# DS112-1_0-B.net
KiCad netlist of a schematic drawn in Altium Designer
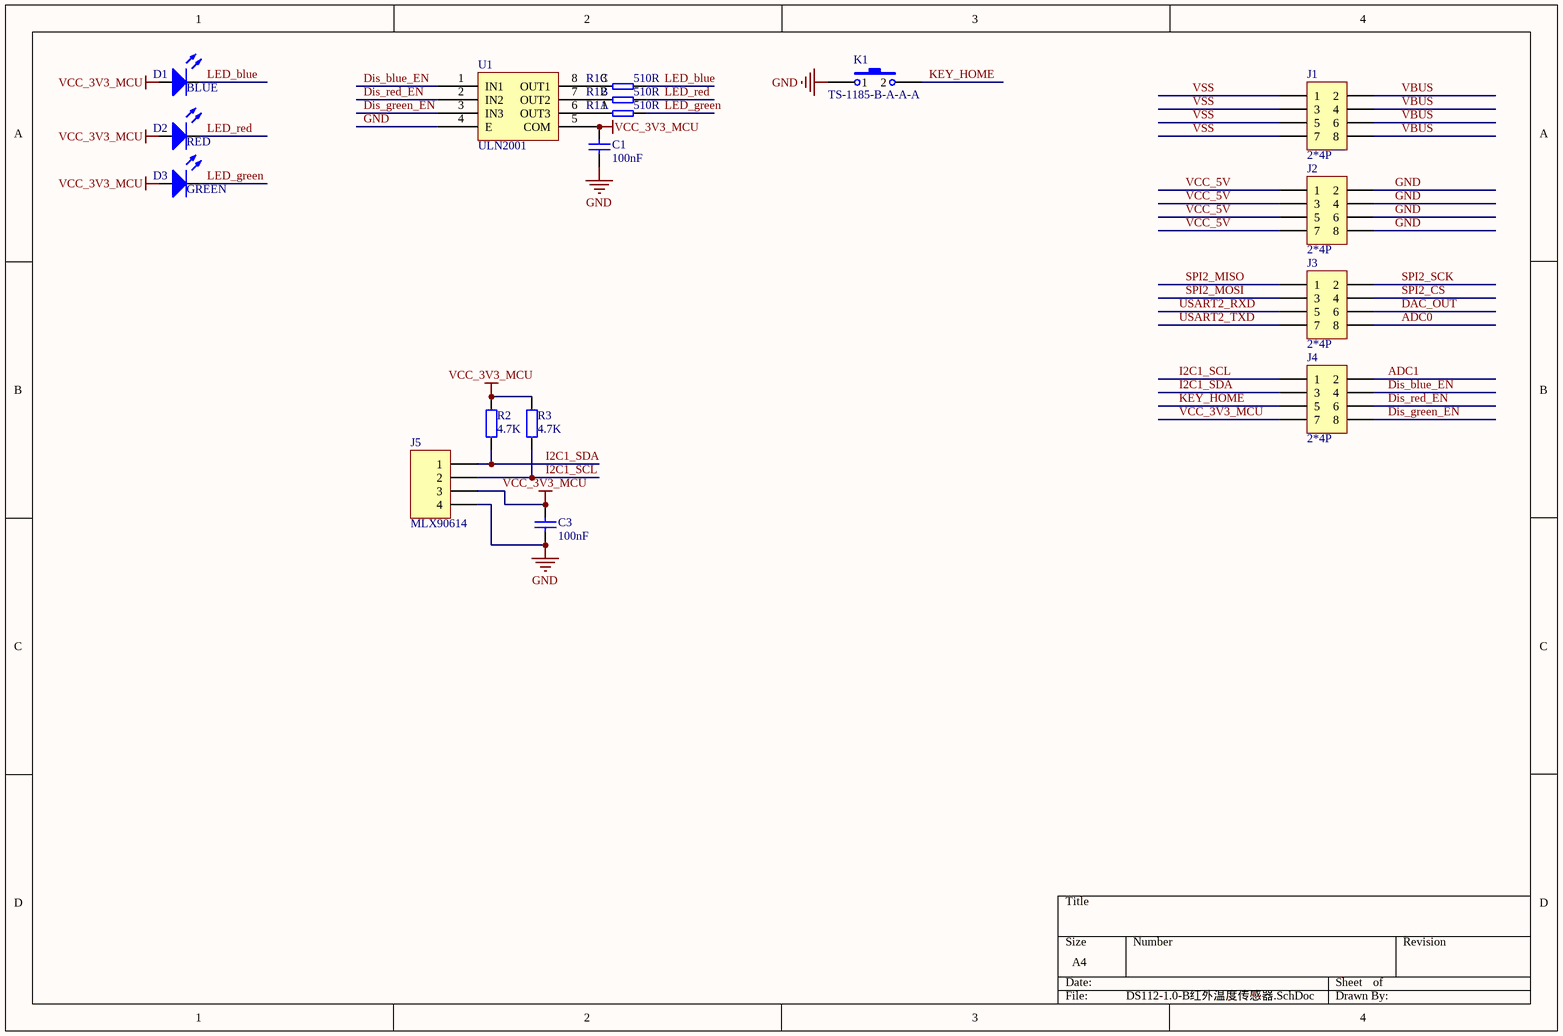
[diagram p0: DS112-1.0-B红外温度传感器.SchDoc]

(export (version "E")
  (design (tool "Eeschema 10.0.6"))
  (components
    (comp (ref "C1")
      (value "100nF")
      (footprint "0603CAP")
      (description "贴片电容")
      (fields (field (name "Comment") "SMDCAP00013"))
      (libsource (lib "AD_SCH") (part "MLCC 100nF 50V ±10％ 0603"))
    )
    (comp (ref "C3")
      (value "100nF")
      (footprint "0603CAP")
      (description "贴片电容")
      (fields (field (name "Comment") "SMDCAP00013"))
      (libsource (lib "AD_SCH") (part "MLCC 100nF 50V ±10％ 0603"))
    )
    (comp (ref "D1")
      (value "BLUE")
      (footprint "LED_0805")
      (description "贴片LED")
      (fields (field (name "Comment") "SMDLED00010"))
      (libsource (lib "AD_SCH") (part "Chip 蓝色LED 0805"))
    )
    (comp (ref "D2")
      (value "RED")
      (footprint "LED_0805")
      (description "贴片LED")
      (fields (field (name "Comment") "SMDLED00003"))
      (libsource (lib "AD_SCH") (part "Chip 红色LED 0805"))
    )
    (comp (ref "D3")
      (value "GREEN")
      (footprint "LED_0805")
      (description "贴片LED")
      (fields (field (name "Comment") "Chip 翠绿LED 0805"))
      (libsource (lib "AD_SCH") (part "Chip 翠绿LED 0805"))
    )
    (comp (ref "J1")
      (value "2*4P")
      (footprint "X1321WVS-2x04J-C40D53")
      (description "双排针2x4P 立贴 1.27mm")
      (fields (field (name "Comment") "X1321WVS-2x04J-C40D53"))
      (libsource (lib "AD_SCH") (part "X1321WVS-2x04J-C40D53"))
    )
    (comp (ref "J2")
      (value "2*4P")
      (footprint "X1321WVS-2x04J-C40D53")
      (description "双排针2x4P 立贴 1.27mm")
      (fields (field (name "Comment") "X1321WVS-2x04J-C40D53"))
      (libsource (lib "AD_SCH") (part "X1321WVS-2x04J-C40D53"))
    )
    (comp (ref "J3")
      (value "2*4P")
      (footprint "X1321WVS-2x04J-C40D53")
      (description "双排针2x4P 立贴 1.27mm")
      (fields (field (name "Comment") "X1321WVS-2x04J-C40D53"))
      (libsource (lib "AD_SCH") (part "X1321WVS-2x04J-C40D53"))
    )
    (comp (ref "J4")
      (value "2*4P")
      (footprint "X1321WVS-2x04J-C40D53")
      (description "双排针2x4P 立贴 1.27mm")
      (fields (field (name "Comment") "X1321WVS-2x04J-C40D53"))
      (libsource (lib "AD_SCH") (part "X1321WVS-2x04J-C40D53"))
    )
    (comp (ref "J5")
      (value "MLX90614")
      (footprint "SIP4")
      (description "单排母座")
      (fields (field (name "Comment") "SL000000047"))
      (libsource (lib "AD_SCH") (part "DIP4 单排母座 间距2.54mm 铜"))
    )
    (comp (ref "K1")
      (value "TS-1185-B-A-A-A")
      (footprint "KEY_TS-1185-x-A-A-A")
      (description "轻触开关")
      (libsource (lib "AD_SCH") (part "TS-1185-B-A-A-A"))
    )
    (comp (ref "R1")
      (value "510R")
      (footprint "0603RES_Pack4")
      (description "贴片排阻")
      (fields (field (name "Comment") "SMDRES05003"))
      (libsource (lib "AD_SCH") (part "Chip R*4 510R 1/16W ±5％ 0603"))
    )
    (comp (ref "R2")
      (value "4.7K")
      (footprint "0603RES")
      (description "贴片电阻")
      (fields (field (name "Comment") "SMDRES00047"))
      (libsource (lib "AD_SCH") (part "Chip 4.7K 1/16W ±1％ 0603"))
    )
    (comp (ref "R3")
      (value "4.7K")
      (footprint "0603RES")
      (description "贴片电阻")
      (fields (field (name "Comment") "SMDRES00047"))
      (libsource (lib "AD_SCH") (part "Chip 4.7K 1/16W ±1％ 0603"))
    )
    (comp (ref "U1")
      (value "ULN2001")
      (footprint "SO-8")
      (description "电机驱动芯片")
      (fields (field (name "Comment") "SMDIC000018"))
      (libsource (lib "AD_SCH") (part "ULN2001 SOP-8"))
    )
  )
  (nets
    (net (code "1") (name "/ADC0") (class "Default")
      (node (ref "J3") (pin "8") (pinfunction "8_8") (pintype "passive"))
    )
    (net (code "2") (name "/ADC1") (class "Default")
      (node (ref "J4") (pin "2") (pinfunction "2_2") (pintype "passive"))
    )
    (net (code "3") (name "/DAC_OUT") (class "Default")
      (node (ref "J3") (pin "6") (pinfunction "6_6") (pintype "passive"))
    )
    (net (code "4") (name "/Dis_blue_EN") (class "Default")
      (node (ref "J4") (pin "4") (pinfunction "4_4") (pintype "passive"))
      (node (ref "U1") (pin "1") (pinfunction "IN1_1") (pintype "passive"))
    )
    (net (code "5") (name "/Dis_green_EN") (class "Default")
      (node (ref "J4") (pin "8") (pinfunction "8_8") (pintype "passive"))
      (node (ref "U1") (pin "3") (pinfunction "IN3_3") (pintype "passive"))
    )
    (net (code "6") (name "/Dis_red_EN") (class "Default")
      (node (ref "J4") (pin "6") (pinfunction "6_6") (pintype "passive"))
      (node (ref "U1") (pin "2") (pinfunction "IN2_2") (pintype "passive"))
    )
    (net (code "7") (name "/I2C1_SCL") (class "Default")
      (node (ref "J4") (pin "1") (pinfunction "1_1") (pintype "passive"))
      (node (ref "J5") (pin "2") (pinfunction "2_2") (pintype "passive"))
      (node (ref "R3") (pin "1") (pinfunction "1_1") (pintype "passive"))
    )
    (net (code "8") (name "/I2C1_SDA") (class "Default")
      (node (ref "J4") (pin "3") (pinfunction "3_3") (pintype "passive"))
      (node (ref "J5") (pin "1") (pinfunction "1_1") (pintype "passive"))
      (node (ref "R2") (pin "1") (pinfunction "1_1") (pintype "passive"))
    )
    (net (code "9") (name "/KEY_HOME") (class "Default")
      (node (ref "J4") (pin "5") (pinfunction "5_5") (pintype "passive"))
      (node (ref "K1") (pin "2") (pinfunction "2_2") (pintype "passive"))
    )
    (net (code "10") (name "/LED_blue") (class "Default")
      (node (ref "D1") (pin "2") (pinfunction "K_2") (pintype "passive"))
      (node (ref "R1") (pin "6") (pinfunction "6_6") (pintype "passive"))
    )
    (net (code "11") (name "/LED_green") (class "Default")
      (node (ref "D3") (pin "2") (pinfunction "K_2") (pintype "passive"))
      (node (ref "R1") (pin "8") (pinfunction "8_8") (pintype "passive"))
    )
    (net (code "12") (name "/LED_red") (class "Default")
      (node (ref "D2") (pin "2") (pinfunction "K_2") (pintype "passive"))
      (node (ref "R1") (pin "7") (pinfunction "7_7") (pintype "passive"))
    )
    (net (code "13") (name "/SPI2_CS") (class "Default")
      (node (ref "J3") (pin "4") (pinfunction "4_4") (pintype "passive"))
    )
    (net (code "14") (name "/SPI2_MISO") (class "Default")
      (node (ref "J3") (pin "1") (pinfunction "1_1") (pintype "passive"))
    )
    (net (code "15") (name "/SPI2_MOSI") (class "Default")
      (node (ref "J3") (pin "3") (pinfunction "3_3") (pintype "passive"))
    )
    (net (code "16") (name "/SPI2_SCK") (class "Default")
      (node (ref "J3") (pin "2") (pinfunction "2_2") (pintype "passive"))
    )
    (net (code "17") (name "/USART2_RXD") (class "Default")
      (node (ref "J3") (pin "5") (pinfunction "5_5") (pintype "passive"))
    )
    (net (code "18") (name "/USART2_TXD") (class "Default")
      (node (ref "J3") (pin "7") (pinfunction "7_7") (pintype "passive"))
    )
    (net (code "19") (name "/VBUS") (class "Default")
      (node (ref "J1") (pin "2") (pinfunction "2_2") (pintype "passive"))
      (node (ref "J1") (pin "4") (pinfunction "4_4") (pintype "passive"))
      (node (ref "J1") (pin "6") (pinfunction "6_6") (pintype "passive"))
      (node (ref "J1") (pin "8") (pinfunction "8_8") (pintype "passive"))
    )
    (net (code "20") (name "/VCC_5V") (class "Default")
      (node (ref "J2") (pin "1") (pinfunction "1_1") (pintype "passive"))
      (node (ref "J2") (pin "3") (pinfunction "3_3") (pintype "passive"))
      (node (ref "J2") (pin "5") (pinfunction "5_5") (pintype "passive"))
      (node (ref "J2") (pin "7") (pinfunction "7_7") (pintype "passive"))
    )
    (net (code "21") (name "/VSS") (class "Default")
      (node (ref "J1") (pin "1") (pinfunction "1_1") (pintype "passive"))
      (node (ref "J1") (pin "3") (pinfunction "3_3") (pintype "passive"))
      (node (ref "J1") (pin "5") (pinfunction "5_5") (pintype "passive"))
      (node (ref "J1") (pin "7") (pinfunction "7_7") (pintype "passive"))
    )
    (net (code "22") (name "GND") (class "Default")
      (node (ref "C1") (pin "1") (pinfunction "1_1") (pintype "passive"))
      (node (ref "C3") (pin "1") (pinfunction "1_1") (pintype "passive"))
      (node (ref "J2") (pin "2") (pinfunction "2_2") (pintype "passive"))
      (node (ref "J2") (pin "4") (pinfunction "4_4") (pintype "passive"))
      (node (ref "J2") (pin "6") (pinfunction "6_6") (pintype "passive"))
      (node (ref "J2") (pin "8") (pinfunction "8_8") (pintype "passive"))
      (node (ref "J5") (pin "4") (pinfunction "4_4") (pintype "passive"))
      (node (ref "K1") (pin "1") (pinfunction "1_1") (pintype "passive"))
      (node (ref "U1") (pin "4") (pinfunction "E_4") (pintype "passive"))
    )
    (net (code "23") (name "Net-(U1-OUT1)") (class "Default")
      (node (ref "R1") (pin "3") (pinfunction "3_3") (pintype "passive"))
      (node (ref "U1") (pin "8") (pinfunction "OUT1_8") (pintype "passive"))
    )
    (net (code "24") (name "Net-(U1-OUT2)") (class "Default")
      (node (ref "R1") (pin "2") (pinfunction "2_2") (pintype "passive"))
      (node (ref "U1") (pin "7") (pinfunction "OUT2_7") (pintype "passive"))
    )
    (net (code "25") (name "Net-(U1-OUT3)") (class "Default")
      (node (ref "R1") (pin "1") (pinfunction "1_1") (pintype "passive"))
      (node (ref "U1") (pin "6") (pinfunction "OUT3_6") (pintype "passive"))
    )
    (net (code "26") (name "VCC_3V3_MCU") (class "Default")
      (node (ref "C1") (pin "2") (pinfunction "2_2") (pintype "passive"))
      (node (ref "C3") (pin "2") (pinfunction "2_2") (pintype "passive"))
      (node (ref "D1") (pin "1") (pinfunction "A_1") (pintype "passive"))
      (node (ref "D2") (pin "1") (pinfunction "A_1") (pintype "passive"))
      (node (ref "D3") (pin "1") (pinfunction "A_1") (pintype "passive"))
      (node (ref "J4") (pin "7") (pinfunction "7_7") (pintype "passive"))
      (node (ref "J5") (pin "3") (pinfunction "3_3") (pintype "passive"))
      (node (ref "R2") (pin "2") (pinfunction "2_2") (pintype "passive"))
      (node (ref "R3") (pin "2") (pinfunction "2_2") (pintype "passive"))
      (node (ref "U1") (pin "5") (pinfunction "COM_5") (pintype "passive"))
    )
  )
)
